# Esquematico_MOSFET.net
KiCad netlist of a schematic drawn in Altium Designer
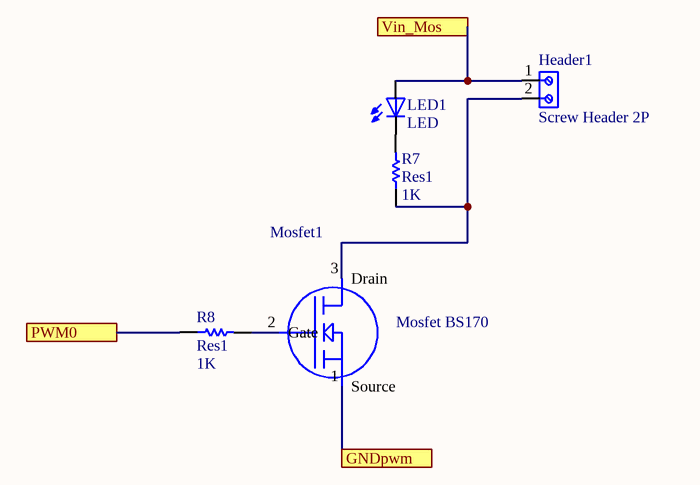
[diagram p0: Esquematico_MOSFET.SchDoc]

(export (version "E")
  (design (tool "Eeschema 10.0.6"))
  (components
    (comp (ref "Header1")
      (value "Screw Header 2P")
      (footprint "Screw Header 2 Posicoes")
      (libsource (lib "myLibAltium") (part "Screw Header 2P"))
    )
    (comp (ref "LED1") (value "LED") (footprint "Led_THT") (libsource (lib "myLibAltium") (part "LED")))
    (comp (ref "Mosfet1")
      (value "Mosfet BS170")
      (footprint "Mosfet BS170")
      (libsource (lib "myLibAltium") (part "Mosfet BS170"))
    )
    (comp (ref "R7")
      (value "Res1")
      (footprint "AXIAL-0.3")
      (description "Resistor")
      (fields (field (name "ALTIUM_VALUE") "1K") (field (name "PUBLISHER") "Altium Limited"))
      (libsource (lib "Miscellaneous Devices") (part "Res1"))
    )
    (comp (ref "R8")
      (value "Res1")
      (footprint "AXIAL-0.3")
      (description "Resistor")
      (fields (field (name "ALTIUM_VALUE") "1K") (field (name "PUBLISHER") "Altium Limited"))
      (libsource (lib "Miscellaneous Devices") (part "Res1"))
    )
  )
  (nets
    (net (code "1") (name "/GNDpwm") (class "Default")
      (node (ref "Mosfet1") (pin "1") (pinfunction "Source_1") (pintype "passive"))
    )
    (net (code "2") (name "/PWM0") (class "Default")
      (node (ref "R8") (pin "1") (pinfunction "1_1") (pintype "passive"))
    )
    (net (code "3") (name "/Vin_Mos") (class "Default")
      (node (ref "Header1") (pin "1") (pinfunction "1_1") (pintype "passive"))
      (node (ref "LED1") (pin "A") (pinfunction "A_A") (pintype "passive"))
    )
    (net (code "4") (name "Net-(LED1-C)") (class "Default")
      (node (ref "LED1") (pin "K") (pinfunction "C_K") (pintype "passive"))
      (node (ref "R7") (pin "2") (pinfunction "2_2") (pintype "passive"))
    )
    (net (code "5") (name "Net-(Mosfet1-Drain)") (class "Default")
      (node (ref "Header1") (pin "2") (pinfunction "2_2") (pintype "passive"))
      (node (ref "Mosfet1") (pin "3") (pinfunction "Drain_3") (pintype "passive"))
      (node (ref "R7") (pin "1") (pinfunction "1_1") (pintype "passive"))
    )
    (net (code "6") (name "Net-(Mosfet1-Gate)") (class "Default")
      (node (ref "Mosfet1") (pin "2") (pinfunction "Gate_2") (pintype "passive"))
      (node (ref "R8") (pin "2") (pinfunction "2_2") (pintype "passive"))
    )
  )
)
